# Power_Management_1.net
KiCad netlist of a schematic drawn in Altium Designer
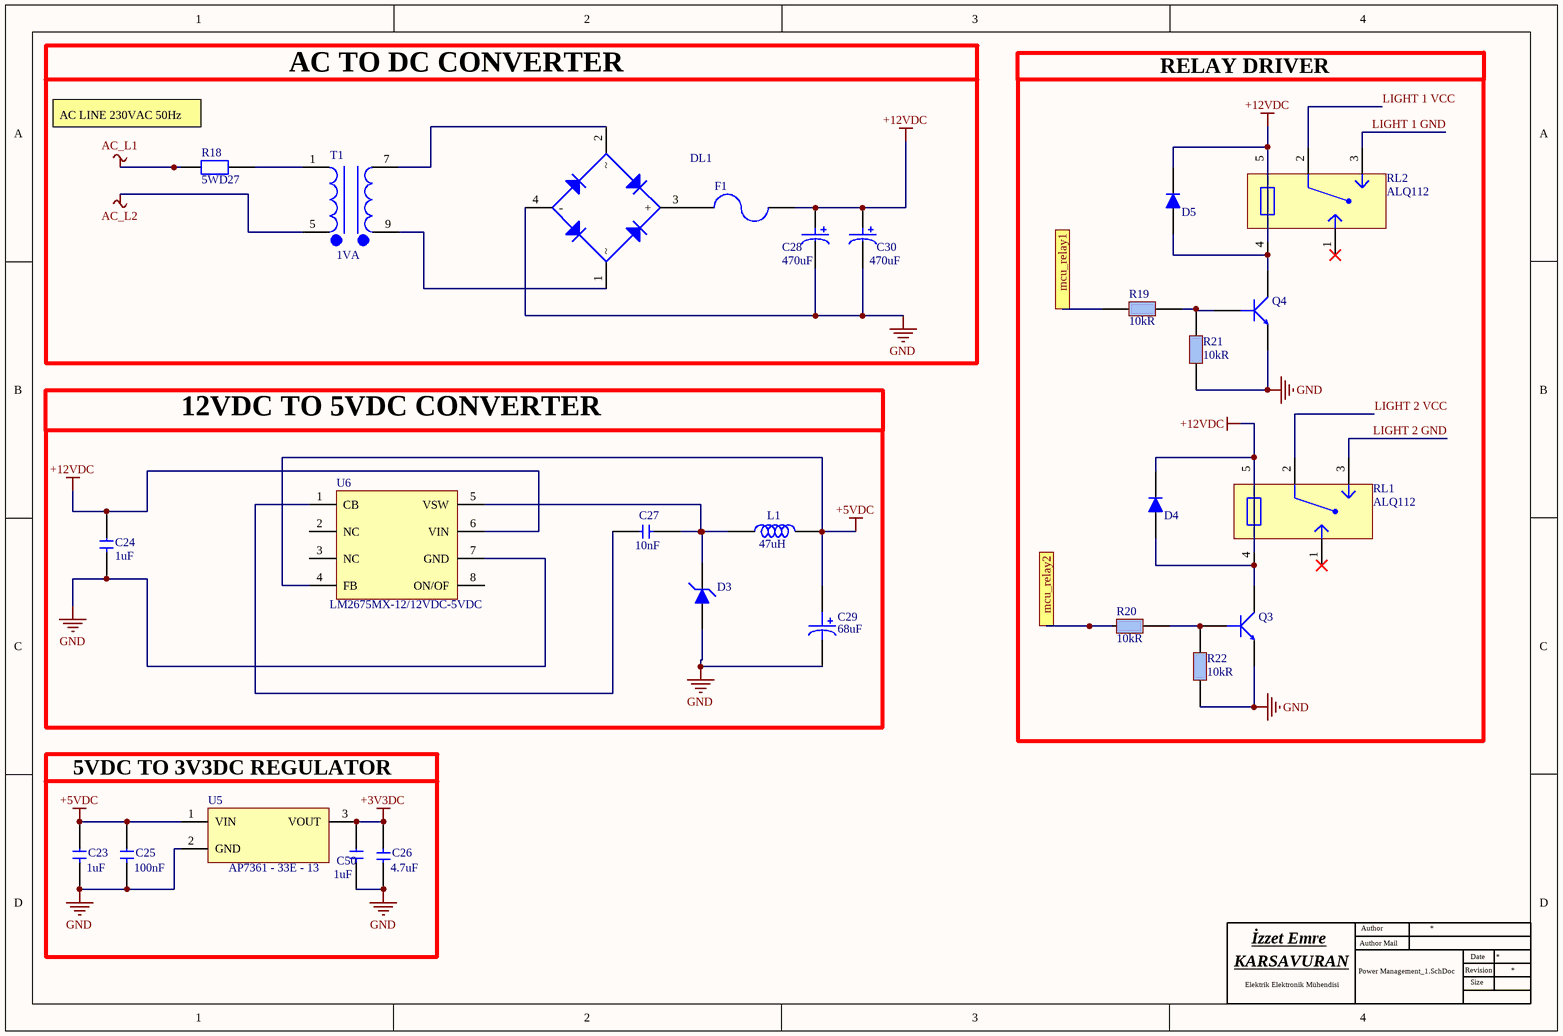
[diagram p0: Power Management_1.SchDoc]

(export (version "E")
  (design (tool "Eeschema 10.0.6"))
  (components
    (comp (ref "C23")
      (value "CL21B105KBFNNNE")
      (footprint "CAP_0805")
      (fields
        (field (name "MANUFACTURER") "Samsung")
        (field (name "TOLERANCE") "10%")
        (field (name "VOLTAGE") "50V")
        (field (name "CAPACITANCE") "1uF")
        (field (name "DESIGNED BY") "İzzet Emre KARSAVURAN")
      )
      (libsource (lib "burglar_alarm_system_Library") (part "CAP CER 1uF"))
    )
    (comp (ref "C24")
      (value "CL21B105KBFNNNE")
      (footprint "CAP_0805")
      (fields
        (field (name "MANUFACTURER") "Samsung")
        (field (name "TOLERANCE") "10%")
        (field (name "VOLTAGE") "50V")
        (field (name "CAPACITANCE") "1uF")
        (field (name "DESIGNED BY") "İzzet Emre KARSAVURAN")
      )
      (libsource (lib "burglar_alarm_system_Library") (part "CAP CER 1uF"))
    )
    (comp (ref "C25")
      (value "CL21B104KBCNNNC")
      (footprint "CAP_0805")
      (fields
        (field (name "MANUFACTURER") "Samsung")
        (field (name "TOLERANCE") "10%")
        (field (name "VOLTAGE") "50V")
        (field (name "CAPACITANCE") "100nF")
        (field (name "DESIGNED BY") "İzzet Emre KARSAVURAN")
      )
      (libsource (lib "burglar_alarm_system_Library") (part "CAP CER 100nF-0803"))
    )
    (comp (ref "C26")
      (value "CL21A475KAQNNNE")
      (footprint "CAP_0805")
      (fields
        (field (name "MANUFACTURER") "Samsung")
        (field (name "TOLERANCE") "10%")
        (field (name "CAPACITANCE") "4.7uF")
        (field (name "DESIGNED BY") "İzzet Emre KARSAVURAN")
      )
      (libsource (lib "burglar_alarm_system_Library") (part "CAP CER 4.7uF"))
    )
    (comp (ref "C27")
      (value "0603B103K160CT")
      (footprint "CAP_0603")
      (fields
        (field (name "MANUFACTURER") "Walsin Technologies")
        (field (name "TOLERANCE") "10%")
        (field (name "CAPACITANCE") "10nF")
        (field (name "DESIGNED BY") "İzzet Emre KARSAVURAN")
      )
      (libsource (lib "burglar_alarm_system_Library") (part "CAP CER 10nF"))
    )
    (comp (ref "C28")
      (value "ESH477M050AH4AA")
      (footprint "CAP_RADIAL_D10_P5")
      (description "Cap, 470UF, 50V, Alu Elec, Radial")
      (fields
        (field (name "MANUFACTURER") "KEMET")
        (field (name "TOLERANCE") "20%")
        (field (name "CAPACITANCE") "470uF")
        (field (name "DESIGNED BY") "İzzet Emre KARSAVURAN")
      )
      (libsource (lib "burglar_alarm_system_Library") (part "CAP ALU ELEC 470uF 50V"))
    )
    (comp (ref "C29")
      (value "EEV686M035A9HAA")
      (footprint "CAP_EEVseries")
      (description "Cap Aluminum Lytic 68uF 35V 20% (6.3 X 7.7mm) SMD 280mA 2000h 105C T/R")
      (fields
        (field (name "MANUFACTURER") "KEMET")
        (field (name "TOLERANCE") "20%")
        (field (name "CAPACITANCE") "68uF")
        (field (name "DESIGNED BY") "İzzet Emre KARSAVURAN")
      )
      (libsource (lib "burglar_alarm_system_Library") (part "CAP ALU 68uF"))
    )
    (comp (ref "C30")
      (value "ESH477M050AH4AA")
      (footprint "CAP_RADIAL_D10_P5")
      (description "Cap, 470UF, 50V, Alu Elec, Radial")
      (fields
        (field (name "MANUFACTURER") "KEMET")
        (field (name "TOLERANCE") "20%")
        (field (name "CAPACITANCE") "470uF")
        (field (name "DESIGNED BY") "İzzet Emre KARSAVURAN")
      )
      (libsource (lib "burglar_alarm_system_Library") (part "CAP ALU ELEC 470uF 50V"))
    )
    (comp (ref "C50")
      (value "CL21B105KBFNNNE")
      (footprint "CAP_0805")
      (fields
        (field (name "MANUFACTURER") "Samsung")
        (field (name "TOLERANCE") "10%")
        (field (name "VOLTAGE") "50V")
        (field (name "CAPACITANCE") "1uF")
        (field (name "DESIGNED BY") "İzzet Emre KARSAVURAN")
      )
      (libsource (lib "burglar_alarm_system_Library") (part "CAP CER 1uF"))
    )
    (comp (ref "D3")
      (value "1SMB5919BT3G")
      (footprint "SMB")
      (description "Diode Zener Single 5.6V 5% 3W 2-Pin SMB T/R")
      (fields
        (field (name "MANUFACTURER") "ON Semiconductor")
        (field (name "TOLERANCE") "5%")
        (field (name "DESIGNED BY") "İzzet Emre KARSAVURAN")
      )
      (libsource (lib "burglar_alarm_system_Library") (part "1SMB5919BT3G"))
    )
    (comp (ref "D4")
      (value "1N4148WS")
      (footprint "SOT23-F")
      (description "ON SEMICONDUCTOR - 1N4148WS - Small Signal Diode, Single, 75 V, 150 mA, 1 V, 4 ns")
      (fields
        (field (name "MANUFACTURER") "ON Semiconductor / Fairchild")
        (field (name "DESIGNED BY") "İzzet Emre KARSAVURAN")
      )
      (libsource (lib "burglar_alarm_system_Library") (part "1N4148WS"))
    )
    (comp (ref "D5")
      (value "1N4148WS")
      (footprint "SOT23-F")
      (description "ON SEMICONDUCTOR - 1N4148WS - Small Signal Diode, Single, 75 V, 150 mA, 1 V, 4 ns")
      (fields
        (field (name "MANUFACTURER") "ON Semiconductor / Fairchild")
        (field (name "DESIGNED BY") "İzzet Emre KARSAVURAN")
      )
      (libsource (lib "burglar_alarm_system_Library") (part "1N4148WS"))
    )
    (comp (ref "DL1")
      (value "DB105STR")
      (footprint "DB-S/DB105STR")
      (description "BRIDGE RECT 1PHASE 600V 1A DB-S")
      (fields (field (name "DESIGNED BY") "İzzet Emre KARSAVRAN"))
      (libsource (lib "burglar_alarm_system_Library") (part "DB105STR"))
    )
    (comp (ref "F1")
      (value "Fulse_3413.0216.22")
      (footprint "1206_Fulse")
      (description "FUSE BRD MNT 1A 32VAC 63VDC 1206")
      (fields
        (field (name "MANUFACTURER") "Schurter")
        (field (name "MANUFACTURER PART NUMBER") "3413.0216.22")
        (field (name "DESIGNED BY") "İzzet Emre KARSAVURAN")
      )
      (libsource (lib "burglar_alarm_system_Library") (part "Fulse_3413.0216.22"))
    )
    (comp (ref "L1")
      (value "78438335470")
      (footprint "IND_1212")
      (description "FIXED IND 47UH 390MA 2.3 OHM SMD")
      (fields
        (field (name "MANUFACTURER") "Wurth Electronics")
        (field (name "TOLERANCE") "30%")
        (field (name "INDUCTANCE") "47uH")
        (field (name "DESIGNED BY") "İzzet Emre KARSAVURAN")
      )
      (libsource (lib "burglar_alarm_system_Library") (part "IND 47uH"))
    )
    (comp (ref "Q3")
      (value "MMBT3904-7-F")
      (footprint "SOT23-F")
      (description "TRANS NPN 40V 0.2A SMD SOT23-3")
      (fields
        (field (name "MANUFACTURER") "Diodes Zetex")
        (field (name "DESIGNED BY") "İzzet Emre KARSAVURAN")
      )
      (libsource (lib "burglar_alarm_system_Library") (part "MMBT3904-7-F"))
    )
    (comp (ref "Q4")
      (value "MMBT3904-7-F")
      (footprint "SOT23-F")
      (description "TRANS NPN 40V 0.2A SMD SOT23-3")
      (fields
        (field (name "MANUFACTURER") "Diodes Zetex")
        (field (name "DESIGNED BY") "İzzet Emre KARSAVURAN")
      )
      (libsource (lib "burglar_alarm_system_Library") (part "MMBT3904-7-F"))
    )
    (comp (ref "R18")
      (value "5WD27")
      (footprint "RES_5WD27")
      (description "RESISTOR 5 WATT CERMET WIREWOUND FLAMEPROOF .27 OHM 5% AXIAL LEAD")
      (fields
        (field (name "MANUFACTURER") "NTE Electronics")
        (field (name "TOLERANCE") "5%")
        (field (name "DESIGNED BY") "İzzet Emre Karsavuran")
      )
      (libsource (lib "burglar_alarm_system_Library") (part "5WD27"))
    )
    (comp (ref "R19")
      (value "RC0603FR-0710KL")
      (footprint "RES_0603")
      (description "Res General Purpose Thick Film 0603 10K Ohm 1% 1/10W ±100ppm/°C Molded SMD Paper T/R")
      (fields
        (field (name "MANUFACTURER") "Yageo")
        (field (name "TOLERANCE") "1%")
        (field (name "RESISTANCE") "10kR")
        (field (name "DESIGNED BY") "İzzet Emre Karsavuran")
      )
      (libsource (lib "burglar_alarm_system_Library") (part "RES 10K OHM 0603"))
    )
    (comp (ref "R20")
      (value "RC0603FR-0710KL")
      (footprint "RES_0603")
      (description "Res General Purpose Thick Film 0603 10K Ohm 1% 1/10W ±100ppm/°C Molded SMD Paper T/R")
      (fields
        (field (name "MANUFACTURER") "Yageo")
        (field (name "TOLERANCE") "1%")
        (field (name "RESISTANCE") "10kR")
        (field (name "DESIGNED BY") "İzzet Emre Karsavuran")
      )
      (libsource (lib "burglar_alarm_system_Library") (part "RES 10K OHM 0603"))
    )
    (comp (ref "R21")
      (value "RC0603FR-0710KL")
      (footprint "RES_0603")
      (description "Res General Purpose Thick Film 0603 10K Ohm 1% 1/10W ±100ppm/°C Molded SMD Paper T/R")
      (fields
        (field (name "MANUFACTURER") "Yageo")
        (field (name "TOLERANCE") "1%")
        (field (name "RESISTANCE") "10kR")
        (field (name "DESIGNED BY") "İzzet Emre Karsavuran")
      )
      (libsource (lib "") (part "RES 10K OHM 0603_1"))
    )
    (comp (ref "R22")
      (value "RC0603FR-0710KL")
      (footprint "RES_0603")
      (description "Res General Purpose Thick Film 0603 10K Ohm 1% 1/10W ±100ppm/°C Molded SMD Paper T/R")
      (fields
        (field (name "MANUFACTURER") "Yageo")
        (field (name "TOLERANCE") "1%")
        (field (name "RESISTANCE") "10kR")
        (field (name "DESIGNED BY") "İzzet Emre Karsavuran")
      )
      (libsource (lib "") (part "RES 10K OHM 0603_1"))
    )
    (comp (ref "RL1")
      (value "ALQ112")
      (footprint "ALQ112")
      (description "PANASONIC - ALQ112 - POWER RELAY, SPDT, 12VDC, 10A, THD")
      (fields (field (name "MANUFACTURER") "Panasonic") (field (name "DESIGNED BY") "İzzet Emre KARSAVURAN"))
      (libsource (lib "burglar_alarm_system_Library") (part "ALQ112"))
    )
    (comp (ref "RL2")
      (value "ALQ112")
      (footprint "ALQ112")
      (description "PANASONIC - ALQ112 - POWER RELAY, SPDT, 12VDC, 10A, THD")
      (fields (field (name "MANUFACTURER") "Panasonic") (field (name "DESIGNED BY") "İzzet Emre KARSAVURAN"))
      (libsource (lib "burglar_alarm_system_Library") (part "ALQ112"))
    )
    (comp (ref "T1")
      (value "BV302S12010")
      (footprint "BV302S")
      (description "PWR XFMR LAMINATED 1VA TH")
      (fields
        (field (name "MANUFACTURER") "Zettler Magnetics")
        (field (name "MANUFACTURER PART NUMBER") "BV302S12010-ZU")
        (field (name "RATED POWER") "1VA")
        (field (name "DESIGNED BY") "İzzet Emre KARSAVURAN")
      )
      (libsource (lib "burglar_alarm_system_Library") (part "BV302S12010"))
    )
    (comp (ref "U5")
      (value "AP7361 - 33E - 13")
      (footprint "SOT223")
      (description "LDO Regulator Pos 3.3V 1A 4-Pin(3+Tab) SOT-223 T/R")
      (fields
        (field (name "MANUFACTURER") "Diodes")
        (field (name "MANUFACTURER PART NUMBER") "AP7361-33E-13")
        (field (name "DESIGNED BY") "İzzet Emre KARSAVURAN")
      )
      (libsource (lib "burglar_alarm_system_Library") (part "AP7361 - 33E - 13"))
    )
    (comp (ref "U6")
      (value "LM2675MX-12/12VDC-5VDC")
      (footprint "SOIC8")
      (description "Buck Switching Regulator IC Positive Adjustable 1.21V 1 Output 1A 8-SOIC (0.154\", 3.90mm Width)")
      (fields
        (field (name "MANUFACTURER") "TI National Semiconductor")
        (field (name "MANUFACTURER PART NUMBER") "LM2675MX-ADJ/NOPB")
        (field (name "DESIGNED BY") "İzzet Emre KARSAVURAN")
      )
      (libsource (lib "burglar_alarm_system_Library") (part "LM2675MX-12/12VDC-5VDC"))
    )
  )
  (nets
    (net (code "1") (name "+3V3DC") (class "Default")
      (node (ref "C26") (pin "2") (pinfunction "2_2") (pintype "passive"))
      (node (ref "C50") (pin "1") (pinfunction "1_1") (pintype "passive"))
      (node (ref "U5") (pin "3") (pinfunction "VOUT_3") (pintype "passive"))
    )
    (net (code "2") (name "+5VDC") (class "Default")
      (node (ref "C23") (pin "1") (pinfunction "1_1") (pintype "passive"))
      (node (ref "C25") (pin "1") (pinfunction "1_1") (pintype "passive"))
      (node (ref "C29") (pin "1") (pinfunction "1_1") (pintype "passive"))
      (node (ref "L1") (pin "2") (pinfunction "2_2") (pintype "passive"))
      (node (ref "U5") (pin "1") (pinfunction "VIN_1") (pintype "passive"))
      (node (ref "U6") (pin "4") (pinfunction "FB_4") (pintype "passive"))
    )
    (net (code "3") (name "+12VDC") (class "Default")
      (node (ref "C24") (pin "1") (pinfunction "1_1") (pintype "passive"))
      (node (ref "C28") (pin "1") (pinfunction "1_1") (pintype "passive"))
      (node (ref "C30") (pin "1") (pinfunction "1_1") (pintype "passive"))
      (node (ref "D4") (pin "1") (pinfunction "1_1") (pintype "power_in"))
      (node (ref "D5") (pin "1") (pinfunction "1_1") (pintype "power_in"))
      (node (ref "F1") (pin "2") (pinfunction "2_2") (pintype "passive"))
      (node (ref "RL1") (pin "5") (pinfunction "5_5") (pintype "passive"))
      (node (ref "RL2") (pin "5") (pinfunction "5_5") (pintype "passive"))
      (node (ref "U6") (pin "6") (pinfunction "VIN_6") (pintype "passive"))
    )
    (net (code "4") (name "/LIGHT 1 GND") (class "Default")
      (node (ref "RL2") (pin "3") (pinfunction "3_3") (pintype "passive"))
    )
    (net (code "5") (name "/LIGHT 1 VCC") (class "Default")
      (node (ref "RL2") (pin "2") (pinfunction "2_2") (pintype "passive"))
    )
    (net (code "6") (name "/LIGHT 2 GND") (class "Default")
      (node (ref "RL1") (pin "3") (pinfunction "3_3") (pintype "passive"))
    )
    (net (code "7") (name "/LIGHT 2 VCC") (class "Default")
      (node (ref "RL1") (pin "2") (pinfunction "2_2") (pintype "passive"))
    )
    (net (code "8") (name "/mcu_relay1") (class "Default")
      (node (ref "R19") (pin "1") (pinfunction "1_1") (pintype "passive"))
    )
    (net (code "9") (name "/mcu_relay2") (class "Default")
      (node (ref "R20") (pin "1") (pinfunction "1_1") (pintype "passive"))
    )
    (net (code "10") (name "AC_L1") (class "Default")
      (node (ref "R18") (pin "1") (pinfunction "1_1") (pintype "passive"))
    )
    (net (code "11") (name "AC_L2") (class "Default")
      (node (ref "T1") (pin "5") (pinfunction "5_5") (pintype "passive"))
    )
    (net (code "12") (name "GND") (class "Default")
      (node (ref "C23") (pin "2") (pinfunction "2_2") (pintype "passive"))
      (node (ref "C24") (pin "2") (pinfunction "2_2") (pintype "passive"))
      (node (ref "C25") (pin "2") (pinfunction "2_2") (pintype "passive"))
      (node (ref "C26") (pin "1") (pinfunction "1_1") (pintype "passive"))
      (node (ref "C28") (pin "2") (pinfunction "2_2") (pintype "passive"))
      (node (ref "C29") (pin "2") (pinfunction "2_2") (pintype "passive"))
      (node (ref "C30") (pin "2") (pinfunction "2_2") (pintype "passive"))
      (node (ref "C50") (pin "2") (pinfunction "2_2") (pintype "passive"))
      (node (ref "D3") (pin "A") (pinfunction "A_A") (pintype "passive"))
      (node (ref "DL1") (pin "4") (pinfunction "-_4") (pintype "passive"))
      (node (ref "Q3") (pin "2") (pinfunction "E_2") (pintype "power_in"))
      (node (ref "Q4") (pin "2") (pinfunction "E_2") (pintype "power_in"))
      (node (ref "R21") (pin "2") (pinfunction "2_2") (pintype "passive"))
      (node (ref "R22") (pin "2") (pinfunction "2_2") (pintype "passive"))
      (node (ref "U5") (pin "2") (pinfunction "GND_2") (pintype "passive"))
      (node (ref "U6") (pin "7") (pinfunction "GND_7") (pintype "passive"))
    )
    (net (code "13") (name "Net-(DL1-+)") (class "Default")
      (node (ref "DL1") (pin "3") (pinfunction "+_3") (pintype "passive"))
      (node (ref "F1") (pin "1") (pinfunction "1_1") (pintype "passive"))
    )
    (net (code "14") (name "Net-(DL1-~-Pad1)") (class "Default")
      (node (ref "DL1") (pin "1") (pinfunction "~_1") (pintype "passive"))
      (node (ref "T1") (pin "9") (pinfunction "9_9") (pintype "passive"))
    )
    (net (code "15") (name "Net-(DL1-~-Pad2)") (class "Default")
      (node (ref "DL1") (pin "2") (pinfunction "~_2") (pintype "passive"))
      (node (ref "T1") (pin "7") (pinfunction "7_7") (pintype "passive"))
    )
    (net (code "16") (name "Net-(Q3-B)") (class "Default")
      (node (ref "Q3") (pin "1") (pinfunction "B_1") (pintype "power_in"))
      (node (ref "R20") (pin "2") (pinfunction "2_2") (pintype "passive"))
      (node (ref "R22") (pin "1") (pinfunction "1_1") (pintype "passive"))
    )
    (net (code "17") (name "Net-(Q3-C)") (class "Default")
      (node (ref "D4") (pin "2") (pinfunction "2_2") (pintype "power_in"))
      (node (ref "Q3") (pin "3") (pinfunction "C_3") (pintype "power_in"))
      (node (ref "RL1") (pin "4") (pinfunction "4_4") (pintype "passive"))
    )
    (net (code "18") (name "Net-(Q4-B)") (class "Default")
      (node (ref "Q4") (pin "1") (pinfunction "B_1") (pintype "power_in"))
      (node (ref "R19") (pin "2") (pinfunction "2_2") (pintype "passive"))
      (node (ref "R21") (pin "1") (pinfunction "1_1") (pintype "passive"))
    )
    (net (code "19") (name "Net-(Q4-C)") (class "Default")
      (node (ref "D5") (pin "2") (pinfunction "2_2") (pintype "power_in"))
      (node (ref "Q4") (pin "3") (pinfunction "C_3") (pintype "power_in"))
      (node (ref "RL2") (pin "4") (pinfunction "4_4") (pintype "passive"))
    )
    (net (code "20") (name "Net-(R18-Pad2)") (class "Default")
      (node (ref "R18") (pin "2") (pinfunction "2_2") (pintype "passive"))
      (node (ref "T1") (pin "1") (pinfunction "1_1") (pintype "passive"))
    )
    (net (code "21") (name "Net-(U6-CB)") (class "Default")
      (node (ref "C27") (pin "1") (pinfunction "1_1") (pintype "passive"))
      (node (ref "U6") (pin "1") (pinfunction "CB_1") (pintype "passive"))
    )
    (net (code "22") (name "Net-(U6-VSW)") (class "Default")
      (node (ref "C27") (pin "2") (pinfunction "2_2") (pintype "passive"))
      (node (ref "D3") (pin "C") (pinfunction "C_C") (pintype "passive"))
      (node (ref "L1") (pin "1") (pinfunction "1_1") (pintype "passive"))
      (node (ref "U6") (pin "5") (pinfunction "VSW_5") (pintype "passive"))
    )
    (net (code "23") (name "unconnected-(RL1-Pad1)") (class "Default")
      (node (ref "RL1") (pin "1") (pinfunction "1_1") (pintype "passive+no_connect"))
    )
    (net (code "24") (name "unconnected-(RL2-Pad1)") (class "Default")
      (node (ref "RL2") (pin "1") (pinfunction "1_1") (pintype "passive+no_connect"))
    )
    (net (code "25") (name "unconnected-(U6-NC-Pad2)") (class "Default")
      (node (ref "U6") (pin "2") (pinfunction "NC_2") (pintype "passive"))
    )
    (net (code "26") (name "unconnected-(U6-NC-Pad3)") (class "Default")
      (node (ref "U6") (pin "3") (pinfunction "NC_3") (pintype "passive"))
    )
    (net (code "27") (name "unconnected-(U6-ON{slash}OF-Pad8)") (class "Default")
      (node (ref "U6") (pin "8") (pinfunction "ON/OF_8") (pintype "passive"))
    )
  )
)
